# LED_Cube_MAX6966.net
KiCad netlist of a schematic drawn in EAGLE
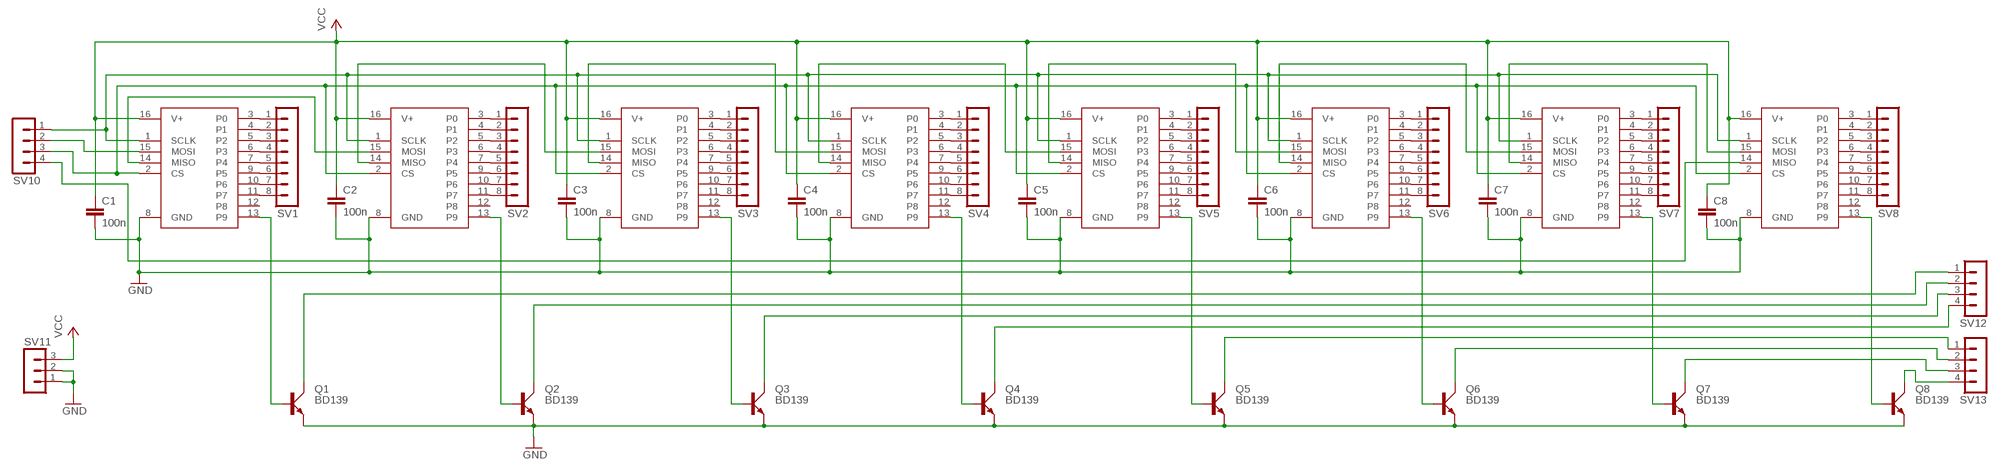
[diagram p0: schematic, sheet 1]

(export (version "E")
  (design (tool "Eeschema 10.0.6"))
  (components
    (comp (ref "C1")
      (value "100n")
      (footprint "eagle-import:C025_050-025X075")
      (libsource (lib "eagle-import") (part "C-EU025_050-025X075"))
    )
    (comp (ref "C2")
      (value "100n")
      (footprint "eagle-import:C025_050-025X075")
      (libsource (lib "eagle-import") (part "C-EU025_050-025X075"))
    )
    (comp (ref "C3")
      (value "100n")
      (footprint "eagle-import:C025_050-025X075")
      (libsource (lib "eagle-import") (part "C-EU025_050-025X075"))
    )
    (comp (ref "C4")
      (value "100n")
      (footprint "eagle-import:C025_050-025X075")
      (libsource (lib "eagle-import") (part "C-EU025_050-025X075"))
    )
    (comp (ref "C5")
      (value "100n")
      (footprint "eagle-import:C025_050-025X075")
      (libsource (lib "eagle-import") (part "C-EU025_050-025X075"))
    )
    (comp (ref "C6")
      (value "100n")
      (footprint "eagle-import:C025_050-025X075")
      (libsource (lib "eagle-import") (part "C-EU025_050-025X075"))
    )
    (comp (ref "C7")
      (value "100n")
      (footprint "eagle-import:C025_050-025X075")
      (libsource (lib "eagle-import") (part "C-EU025_050-025X075"))
    )
    (comp (ref "C8")
      (value "100n")
      (footprint "eagle-import:C025_050-025X075")
      (libsource (lib "eagle-import") (part "C-EU025_050-025X075"))
    )
    (comp (ref "Q1")
      (value "BD139")
      (footprint "eagle-import:TO126AV")
      (libsource (lib "eagle-import") (part "BD139"))
    )
    (comp (ref "Q2")
      (value "BD139")
      (footprint "eagle-import:TO126AV")
      (libsource (lib "eagle-import") (part "BD139"))
    )
    (comp (ref "Q3")
      (value "BD139")
      (footprint "eagle-import:TO126AV")
      (libsource (lib "eagle-import") (part "BD139"))
    )
    (comp (ref "Q4")
      (value "BD139")
      (footprint "eagle-import:TO126AV")
      (libsource (lib "eagle-import") (part "BD139"))
    )
    (comp (ref "Q5")
      (value "BD139")
      (footprint "eagle-import:TO126AV")
      (libsource (lib "eagle-import") (part "BD139"))
    )
    (comp (ref "Q6")
      (value "BD139")
      (footprint "eagle-import:TO126AV")
      (libsource (lib "eagle-import") (part "BD139"))
    )
    (comp (ref "Q7")
      (value "BD139")
      (footprint "eagle-import:TO126AV")
      (libsource (lib "eagle-import") (part "BD139"))
    )
    (comp (ref "Q8")
      (value "BD139")
      (footprint "eagle-import:TO126AV")
      (libsource (lib "eagle-import") (part "BD139"))
    )
    (comp (ref "SV1")
      (value "MA08-1")
      (footprint "eagle-import:MA08-1")
      (libsource (lib "eagle-import") (part "MA08-1"))
    )
    (comp (ref "SV2")
      (value "MA08-1")
      (footprint "eagle-import:MA08-1")
      (libsource (lib "eagle-import") (part "MA08-1"))
    )
    (comp (ref "SV3")
      (value "MA08-1")
      (footprint "eagle-import:MA08-1")
      (libsource (lib "eagle-import") (part "MA08-1"))
    )
    (comp (ref "SV4")
      (value "MA08-1")
      (footprint "eagle-import:MA08-1")
      (libsource (lib "eagle-import") (part "MA08-1"))
    )
    (comp (ref "SV5")
      (value "MA08-1")
      (footprint "eagle-import:MA08-1")
      (libsource (lib "eagle-import") (part "MA08-1"))
    )
    (comp (ref "SV6")
      (value "MA08-1")
      (footprint "eagle-import:MA08-1")
      (libsource (lib "eagle-import") (part "MA08-1"))
    )
    (comp (ref "SV7")
      (value "MA08-1")
      (footprint "eagle-import:MA08-1")
      (libsource (lib "eagle-import") (part "MA08-1"))
    )
    (comp (ref "SV8")
      (value "MA08-1")
      (footprint "eagle-import:MA08-1")
      (libsource (lib "eagle-import") (part "MA08-1"))
    )
    (comp (ref "SV10")
      (value "MA04-1")
      (footprint "eagle-import:MA04-1")
      (libsource (lib "eagle-import") (part "MA04-1"))
    )
    (comp (ref "SV11")
      (value "MA03-1")
      (footprint "eagle-import:MA03-1")
      (libsource (lib "eagle-import") (part "MA03-1"))
    )
    (comp (ref "SV12")
      (value "MA04-1")
      (footprint "eagle-import:MA04-1")
      (libsource (lib "eagle-import") (part "MA04-1"))
    )
    (comp (ref "SV13")
      (value "MA04-1")
      (footprint "eagle-import:MA04-1")
      (libsource (lib "eagle-import") (part "MA04-1"))
    )
    (comp (ref "U$1")
      (value "MAX6966")
      (footprint "eagle-import:QSOP16")
      (libsource (lib "eagle-import") (part "MAX6966"))
    )
    (comp (ref "U$2")
      (value "MAX6966")
      (footprint "eagle-import:QSOP16")
      (libsource (lib "eagle-import") (part "MAX6966"))
    )
    (comp (ref "U$3")
      (value "MAX6966")
      (footprint "eagle-import:QSOP16")
      (libsource (lib "eagle-import") (part "MAX6966"))
    )
    (comp (ref "U$4")
      (value "MAX6966")
      (footprint "eagle-import:QSOP16")
      (libsource (lib "eagle-import") (part "MAX6966"))
    )
    (comp (ref "U$5")
      (value "MAX6966")
      (footprint "eagle-import:QSOP16")
      (libsource (lib "eagle-import") (part "MAX6966"))
    )
    (comp (ref "U$6")
      (value "MAX6966")
      (footprint "eagle-import:QSOP16")
      (libsource (lib "eagle-import") (part "MAX6966"))
    )
    (comp (ref "U$7")
      (value "MAX6966")
      (footprint "eagle-import:QSOP16")
      (libsource (lib "eagle-import") (part "MAX6966"))
    )
    (comp (ref "U$8")
      (value "MAX6966")
      (footprint "eagle-import:QSOP16")
      (libsource (lib "eagle-import") (part "MAX6966"))
    )
  )
  (nets
    (net (code "1") (name "GND") (class "Default")
      (node (ref "C1") (pin "2") (pinfunction "2_2") (pintype "passive"))
      (node (ref "C2") (pin "2") (pinfunction "2_2") (pintype "passive"))
      (node (ref "C3") (pin "2") (pinfunction "2_2") (pintype "passive"))
      (node (ref "C4") (pin "2") (pinfunction "2_2") (pintype "passive"))
      (node (ref "C5") (pin "2") (pinfunction "2_2") (pintype "passive"))
      (node (ref "C6") (pin "2") (pinfunction "2_2") (pintype "passive"))
      (node (ref "C7") (pin "2") (pinfunction "2_2") (pintype "passive"))
      (node (ref "C8") (pin "2") (pinfunction "2_2") (pintype "passive"))
      (node (ref "Q1") (pin "E") (pinfunction "E_E") (pintype "passive"))
      (node (ref "Q2") (pin "E") (pinfunction "E_E") (pintype "passive"))
      (node (ref "Q3") (pin "E") (pinfunction "E_E") (pintype "passive"))
      (node (ref "Q4") (pin "E") (pinfunction "E_E") (pintype "passive"))
      (node (ref "Q5") (pin "E") (pinfunction "E_E") (pintype "passive"))
      (node (ref "Q6") (pin "E") (pinfunction "E_E") (pintype "passive"))
      (node (ref "Q7") (pin "E") (pinfunction "E_E") (pintype "passive"))
      (node (ref "Q8") (pin "E") (pinfunction "E_E") (pintype "passive"))
      (node (ref "SV11") (pin "1") (pinfunction "1_1") (pintype "passive"))
      (node (ref "SV11") (pin "2") (pinfunction "2_2") (pintype "passive"))
      (node (ref "U$1") (pin "8") (pinfunction "GND_8") (pintype "bidirectional"))
      (node (ref "U$2") (pin "8") (pinfunction "GND_8") (pintype "bidirectional"))
      (node (ref "U$3") (pin "8") (pinfunction "GND_8") (pintype "bidirectional"))
      (node (ref "U$4") (pin "8") (pinfunction "GND_8") (pintype "bidirectional"))
      (node (ref "U$5") (pin "8") (pinfunction "GND_8") (pintype "bidirectional"))
      (node (ref "U$6") (pin "8") (pinfunction "GND_8") (pintype "bidirectional"))
      (node (ref "U$7") (pin "8") (pinfunction "GND_8") (pintype "bidirectional"))
      (node (ref "U$8") (pin "8") (pinfunction "GND_8") (pintype "bidirectional"))
    )
    (net (code "2") (name "Net-(Q1-PadC)") (class "Default")
      (node (ref "Q1") (pin "C") (pinfunction "C_C") (pintype "passive"))
      (node (ref "SV12") (pin "1") (pinfunction "1_1") (pintype "passive"))
    )
    (net (code "3") (name "Net-(Q2-PadC)") (class "Default")
      (node (ref "Q2") (pin "C") (pinfunction "C_C") (pintype "passive"))
      (node (ref "SV12") (pin "2") (pinfunction "2_2") (pintype "passive"))
    )
    (net (code "4") (name "Net-(Q3-PadC)") (class "Default")
      (node (ref "Q3") (pin "C") (pinfunction "C_C") (pintype "passive"))
      (node (ref "SV12") (pin "3") (pinfunction "3_3") (pintype "passive"))
    )
    (net (code "5") (name "Net-(Q4-PadC)") (class "Default")
      (node (ref "Q4") (pin "C") (pinfunction "C_C") (pintype "passive"))
      (node (ref "SV12") (pin "4") (pinfunction "4_4") (pintype "passive"))
    )
    (net (code "6") (name "Net-(Q5-PadC)") (class "Default")
      (node (ref "Q5") (pin "C") (pinfunction "C_C") (pintype "passive"))
      (node (ref "SV13") (pin "1") (pinfunction "1_1") (pintype "passive"))
    )
    (net (code "7") (name "Net-(Q6-PadC)") (class "Default")
      (node (ref "Q6") (pin "C") (pinfunction "C_C") (pintype "passive"))
      (node (ref "SV13") (pin "2") (pinfunction "2_2") (pintype "passive"))
    )
    (net (code "8") (name "Net-(Q7-PadC)") (class "Default")
      (node (ref "Q7") (pin "C") (pinfunction "C_C") (pintype "passive"))
      (node (ref "SV13") (pin "3") (pinfunction "3_3") (pintype "passive"))
    )
    (net (code "9") (name "Net-(Q8-PadC)") (class "Default")
      (node (ref "Q8") (pin "C") (pinfunction "C_C") (pintype "passive"))
      (node (ref "SV13") (pin "4") (pinfunction "4_4") (pintype "passive"))
    )
    (net (code "10") (name "Net-(U$1-CS)") (class "Default")
      (node (ref "SV10") (pin "3") (pinfunction "3_3") (pintype "passive"))
      (node (ref "U$1") (pin "2") (pinfunction "CS_2") (pintype "bidirectional"))
      (node (ref "U$2") (pin "2") (pinfunction "CS_2") (pintype "bidirectional"))
      (node (ref "U$3") (pin "2") (pinfunction "CS_2") (pintype "bidirectional"))
      (node (ref "U$4") (pin "2") (pinfunction "CS_2") (pintype "bidirectional"))
      (node (ref "U$5") (pin "2") (pinfunction "CS_2") (pintype "bidirectional"))
      (node (ref "U$6") (pin "2") (pinfunction "CS_2") (pintype "bidirectional"))
      (node (ref "U$7") (pin "2") (pinfunction "CS_2") (pintype "bidirectional"))
      (node (ref "U$8") (pin "2") (pinfunction "CS_2") (pintype "bidirectional"))
    )
    (net (code "11") (name "Net-(U$1-MISO)") (class "Default")
      (node (ref "U$1") (pin "14") (pinfunction "MISO_14") (pintype "bidirectional"))
      (node (ref "U$2") (pin "15") (pinfunction "MOSI_15") (pintype "bidirectional"))
    )
    (net (code "12") (name "Net-(U$1-MOSI)") (class "Default")
      (node (ref "SV10") (pin "2") (pinfunction "2_2") (pintype "passive"))
      (node (ref "U$1") (pin "15") (pinfunction "MOSI_15") (pintype "bidirectional"))
    )
    (net (code "13") (name "Net-(U$1-P0)") (class "Default")
      (node (ref "SV1") (pin "1") (pinfunction "1_1") (pintype "passive"))
      (node (ref "U$1") (pin "3") (pinfunction "P0_3") (pintype "bidirectional"))
    )
    (net (code "14") (name "Net-(U$1-P1)") (class "Default")
      (node (ref "SV1") (pin "2") (pinfunction "2_2") (pintype "passive"))
      (node (ref "U$1") (pin "4") (pinfunction "P1_4") (pintype "bidirectional"))
    )
    (net (code "15") (name "Net-(U$1-P2)") (class "Default")
      (node (ref "SV1") (pin "3") (pinfunction "3_3") (pintype "passive"))
      (node (ref "U$1") (pin "5") (pinfunction "P2_5") (pintype "bidirectional"))
    )
    (net (code "16") (name "Net-(U$1-P3)") (class "Default")
      (node (ref "SV1") (pin "4") (pinfunction "4_4") (pintype "passive"))
      (node (ref "U$1") (pin "6") (pinfunction "P3_6") (pintype "bidirectional"))
    )
    (net (code "17") (name "Net-(U$1-P4)") (class "Default")
      (node (ref "SV1") (pin "5") (pinfunction "5_5") (pintype "passive"))
      (node (ref "U$1") (pin "7") (pinfunction "P4_7") (pintype "bidirectional"))
    )
    (net (code "18") (name "Net-(U$1-P5)") (class "Default")
      (node (ref "SV1") (pin "6") (pinfunction "6_6") (pintype "passive"))
      (node (ref "U$1") (pin "9") (pinfunction "P5_9") (pintype "bidirectional"))
    )
    (net (code "19") (name "Net-(U$1-P6)") (class "Default")
      (node (ref "SV1") (pin "7") (pinfunction "7_7") (pintype "passive"))
      (node (ref "U$1") (pin "10") (pinfunction "P6_10") (pintype "bidirectional"))
    )
    (net (code "20") (name "Net-(U$1-P7)") (class "Default")
      (node (ref "SV1") (pin "8") (pinfunction "8_8") (pintype "passive"))
      (node (ref "U$1") (pin "11") (pinfunction "P7_11") (pintype "bidirectional"))
    )
    (net (code "21") (name "Net-(U$1-P9)") (class "Default")
      (node (ref "Q1") (pin "B") (pinfunction "B_B") (pintype "passive"))
      (node (ref "U$1") (pin "13") (pinfunction "P9_13") (pintype "bidirectional"))
    )
    (net (code "22") (name "Net-(U$1-SCLK)") (class "Default")
      (node (ref "SV10") (pin "1") (pinfunction "1_1") (pintype "passive"))
      (node (ref "U$1") (pin "1") (pinfunction "SCLK_1") (pintype "bidirectional"))
      (node (ref "U$2") (pin "1") (pinfunction "SCLK_1") (pintype "bidirectional"))
      (node (ref "U$3") (pin "1") (pinfunction "SCLK_1") (pintype "bidirectional"))
      (node (ref "U$4") (pin "1") (pinfunction "SCLK_1") (pintype "bidirectional"))
      (node (ref "U$5") (pin "1") (pinfunction "SCLK_1") (pintype "bidirectional"))
      (node (ref "U$6") (pin "1") (pinfunction "SCLK_1") (pintype "bidirectional"))
      (node (ref "U$7") (pin "1") (pinfunction "SCLK_1") (pintype "bidirectional"))
      (node (ref "U$8") (pin "1") (pinfunction "SCLK_1") (pintype "bidirectional"))
    )
    (net (code "23") (name "Net-(U$2-MISO)") (class "Default")
      (node (ref "U$2") (pin "14") (pinfunction "MISO_14") (pintype "bidirectional"))
      (node (ref "U$3") (pin "15") (pinfunction "MOSI_15") (pintype "bidirectional"))
    )
    (net (code "24") (name "Net-(U$2-P0)") (class "Default")
      (node (ref "SV2") (pin "1") (pinfunction "1_1") (pintype "passive"))
      (node (ref "U$2") (pin "3") (pinfunction "P0_3") (pintype "bidirectional"))
    )
    (net (code "25") (name "Net-(U$2-P1)") (class "Default")
      (node (ref "SV2") (pin "2") (pinfunction "2_2") (pintype "passive"))
      (node (ref "U$2") (pin "4") (pinfunction "P1_4") (pintype "bidirectional"))
    )
    (net (code "26") (name "Net-(U$2-P2)") (class "Default")
      (node (ref "SV2") (pin "3") (pinfunction "3_3") (pintype "passive"))
      (node (ref "U$2") (pin "5") (pinfunction "P2_5") (pintype "bidirectional"))
    )
    (net (code "27") (name "Net-(U$2-P3)") (class "Default")
      (node (ref "SV2") (pin "4") (pinfunction "4_4") (pintype "passive"))
      (node (ref "U$2") (pin "6") (pinfunction "P3_6") (pintype "bidirectional"))
    )
    (net (code "28") (name "Net-(U$2-P4)") (class "Default")
      (node (ref "SV2") (pin "5") (pinfunction "5_5") (pintype "passive"))
      (node (ref "U$2") (pin "7") (pinfunction "P4_7") (pintype "bidirectional"))
    )
    (net (code "29") (name "Net-(U$2-P5)") (class "Default")
      (node (ref "SV2") (pin "6") (pinfunction "6_6") (pintype "passive"))
      (node (ref "U$2") (pin "9") (pinfunction "P5_9") (pintype "bidirectional"))
    )
    (net (code "30") (name "Net-(U$2-P6)") (class "Default")
      (node (ref "SV2") (pin "7") (pinfunction "7_7") (pintype "passive"))
      (node (ref "U$2") (pin "10") (pinfunction "P6_10") (pintype "bidirectional"))
    )
    (net (code "31") (name "Net-(U$2-P7)") (class "Default")
      (node (ref "SV2") (pin "8") (pinfunction "8_8") (pintype "passive"))
      (node (ref "U$2") (pin "11") (pinfunction "P7_11") (pintype "bidirectional"))
    )
    (net (code "32") (name "Net-(U$2-P9)") (class "Default")
      (node (ref "Q2") (pin "B") (pinfunction "B_B") (pintype "passive"))
      (node (ref "U$2") (pin "13") (pinfunction "P9_13") (pintype "bidirectional"))
    )
    (net (code "33") (name "Net-(U$3-MISO)") (class "Default")
      (node (ref "U$3") (pin "14") (pinfunction "MISO_14") (pintype "bidirectional"))
      (node (ref "U$4") (pin "15") (pinfunction "MOSI_15") (pintype "bidirectional"))
    )
    (net (code "34") (name "Net-(U$3-P0)") (class "Default")
      (node (ref "SV3") (pin "1") (pinfunction "1_1") (pintype "passive"))
      (node (ref "U$3") (pin "3") (pinfunction "P0_3") (pintype "bidirectional"))
    )
    (net (code "35") (name "Net-(U$3-P1)") (class "Default")
      (node (ref "SV3") (pin "2") (pinfunction "2_2") (pintype "passive"))
      (node (ref "U$3") (pin "4") (pinfunction "P1_4") (pintype "bidirectional"))
    )
    (net (code "36") (name "Net-(U$3-P2)") (class "Default")
      (node (ref "SV3") (pin "3") (pinfunction "3_3") (pintype "passive"))
      (node (ref "U$3") (pin "5") (pinfunction "P2_5") (pintype "bidirectional"))
    )
    (net (code "37") (name "Net-(U$3-P3)") (class "Default")
      (node (ref "SV3") (pin "4") (pinfunction "4_4") (pintype "passive"))
      (node (ref "U$3") (pin "6") (pinfunction "P3_6") (pintype "bidirectional"))
    )
    (net (code "38") (name "Net-(U$3-P4)") (class "Default")
      (node (ref "SV3") (pin "5") (pinfunction "5_5") (pintype "passive"))
      (node (ref "U$3") (pin "7") (pinfunction "P4_7") (pintype "bidirectional"))
    )
    (net (code "39") (name "Net-(U$3-P5)") (class "Default")
      (node (ref "SV3") (pin "6") (pinfunction "6_6") (pintype "passive"))
      (node (ref "U$3") (pin "9") (pinfunction "P5_9") (pintype "bidirectional"))
    )
    (net (code "40") (name "Net-(U$3-P6)") (class "Default")
      (node (ref "SV3") (pin "7") (pinfunction "7_7") (pintype "passive"))
      (node (ref "U$3") (pin "10") (pinfunction "P6_10") (pintype "bidirectional"))
    )
    (net (code "41") (name "Net-(U$3-P7)") (class "Default")
      (node (ref "SV3") (pin "8") (pinfunction "8_8") (pintype "passive"))
      (node (ref "U$3") (pin "11") (pinfunction "P7_11") (pintype "bidirectional"))
    )
    (net (code "42") (name "Net-(U$3-P9)") (class "Default")
      (node (ref "Q3") (pin "B") (pinfunction "B_B") (pintype "passive"))
      (node (ref "U$3") (pin "13") (pinfunction "P9_13") (pintype "bidirectional"))
    )
    (net (code "43") (name "Net-(U$4-MISO)") (class "Default")
      (node (ref "U$4") (pin "14") (pinfunction "MISO_14") (pintype "bidirectional"))
      (node (ref "U$5") (pin "15") (pinfunction "MOSI_15") (pintype "bidirectional"))
    )
    (net (code "44") (name "Net-(U$4-P0)") (class "Default")
      (node (ref "SV4") (pin "1") (pinfunction "1_1") (pintype "passive"))
      (node (ref "U$4") (pin "3") (pinfunction "P0_3") (pintype "bidirectional"))
    )
    (net (code "45") (name "Net-(U$4-P1)") (class "Default")
      (node (ref "SV4") (pin "2") (pinfunction "2_2") (pintype "passive"))
      (node (ref "U$4") (pin "4") (pinfunction "P1_4") (pintype "bidirectional"))
    )
    (net (code "46") (name "Net-(U$4-P2)") (class "Default")
      (node (ref "SV4") (pin "3") (pinfunction "3_3") (pintype "passive"))
      (node (ref "U$4") (pin "5") (pinfunction "P2_5") (pintype "bidirectional"))
    )
    (net (code "47") (name "Net-(U$4-P3)") (class "Default")
      (node (ref "SV4") (pin "4") (pinfunction "4_4") (pintype "passive"))
      (node (ref "U$4") (pin "6") (pinfunction "P3_6") (pintype "bidirectional"))
    )
    (net (code "48") (name "Net-(U$4-P4)") (class "Default")
      (node (ref "SV4") (pin "5") (pinfunction "5_5") (pintype "passive"))
      (node (ref "U$4") (pin "7") (pinfunction "P4_7") (pintype "bidirectional"))
    )
    (net (code "49") (name "Net-(U$4-P5)") (class "Default")
      (node (ref "SV4") (pin "6") (pinfunction "6_6") (pintype "passive"))
      (node (ref "U$4") (pin "9") (pinfunction "P5_9") (pintype "bidirectional"))
    )
    (net (code "50") (name "Net-(U$4-P6)") (class "Default")
      (node (ref "SV4") (pin "7") (pinfunction "7_7") (pintype "passive"))
      (node (ref "U$4") (pin "10") (pinfunction "P6_10") (pintype "bidirectional"))
    )
    (net (code "51") (name "Net-(U$4-P7)") (class "Default")
      (node (ref "SV4") (pin "8") (pinfunction "8_8") (pintype "passive"))
      (node (ref "U$4") (pin "11") (pinfunction "P7_11") (pintype "bidirectional"))
    )
    (net (code "52") (name "Net-(U$4-P9)") (class "Default")
      (node (ref "Q4") (pin "B") (pinfunction "B_B") (pintype "passive"))
      (node (ref "U$4") (pin "13") (pinfunction "P9_13") (pintype "bidirectional"))
    )
    (net (code "53") (name "Net-(U$5-MISO)") (class "Default")
      (node (ref "U$5") (pin "14") (pinfunction "MISO_14") (pintype "bidirectional"))
      (node (ref "U$6") (pin "15") (pinfunction "MOSI_15") (pintype "bidirectional"))
    )
    (net (code "54") (name "Net-(U$5-P0)") (class "Default")
      (node (ref "SV5") (pin "1") (pinfunction "1_1") (pintype "passive"))
      (node (ref "U$5") (pin "3") (pinfunction "P0_3") (pintype "bidirectional"))
    )
    (net (code "55") (name "Net-(U$5-P1)") (class "Default")
      (node (ref "SV5") (pin "2") (pinfunction "2_2") (pintype "passive"))
      (node (ref "U$5") (pin "4") (pinfunction "P1_4") (pintype "bidirectional"))
    )
    (net (code "56") (name "Net-(U$5-P2)") (class "Default")
      (node (ref "SV5") (pin "3") (pinfunction "3_3") (pintype "passive"))
      (node (ref "U$5") (pin "5") (pinfunction "P2_5") (pintype "bidirectional"))
    )
    (net (code "57") (name "Net-(U$5-P3)") (class "Default")
      (node (ref "SV5") (pin "4") (pinfunction "4_4") (pintype "passive"))
      (node (ref "U$5") (pin "6") (pinfunction "P3_6") (pintype "bidirectional"))
    )
    (net (code "58") (name "Net-(U$5-P4)") (class "Default")
      (node (ref "SV5") (pin "5") (pinfunction "5_5") (pintype "passive"))
      (node (ref "U$5") (pin "7") (pinfunction "P4_7") (pintype "bidirectional"))
    )
    (net (code "59") (name "Net-(U$5-P5)") (class "Default")
      (node (ref "SV5") (pin "6") (pinfunction "6_6") (pintype "passive"))
      (node (ref "U$5") (pin "9") (pinfunction "P5_9") (pintype "bidirectional"))
    )
    (net (code "60") (name "Net-(U$5-P6)") (class "Default")
      (node (ref "SV5") (pin "7") (pinfunction "7_7") (pintype "passive"))
      (node (ref "U$5") (pin "10") (pinfunction "P6_10") (pintype "bidirectional"))
    )
    (net (code "61") (name "Net-(U$5-P7)") (class "Default")
      (node (ref "SV5") (pin "8") (pinfunction "8_8") (pintype "passive"))
      (node (ref "U$5") (pin "11") (pinfunction "P7_11") (pintype "bidirectional"))
    )
    (net (code "62") (name "Net-(U$5-P9)") (class "Default")
      (node (ref "Q5") (pin "B") (pinfunction "B_B") (pintype "passive"))
      (node (ref "U$5") (pin "13") (pinfunction "P9_13") (pintype "bidirectional"))
    )
    (net (code "63") (name "Net-(U$6-MISO)") (class "Default")
      (node (ref "U$6") (pin "14") (pinfunction "MISO_14") (pintype "bidirectional"))
      (node (ref "U$7") (pin "15") (pinfunction "MOSI_15") (pintype "bidirectional"))
    )
    (net (code "64") (name "Net-(U$6-P0)") (class "Default")
      (node (ref "SV6") (pin "1") (pinfunction "1_1") (pintype "passive"))
      (node (ref "U$6") (pin "3") (pinfunction "P0_3") (pintype "bidirectional"))
    )
    (net (code "65") (name "Net-(U$6-P1)") (class "Default")
      (node (ref "SV6") (pin "2") (pinfunction "2_2") (pintype "passive"))
      (node (ref "U$6") (pin "4") (pinfunction "P1_4") (pintype "bidirectional"))
    )
    (net (code "66") (name "Net-(U$6-P2)") (class "Default")
      (node (ref "SV6") (pin "3") (pinfunction "3_3") (pintype "passive"))
      (node (ref "U$6") (pin "5") (pinfunction "P2_5") (pintype "bidirectional"))
    )
    (net (code "67") (name "Net-(U$6-P3)") (class "Default")
      (node (ref "SV6") (pin "4") (pinfunction "4_4") (pintype "passive"))
      (node (ref "U$6") (pin "6") (pinfunction "P3_6") (pintype "bidirectional"))
    )
    (net (code "68") (name "Net-(U$6-P4)") (class "Default")
      (node (ref "SV6") (pin "5") (pinfunction "5_5") (pintype "passive"))
      (node (ref "U$6") (pin "7") (pinfunction "P4_7") (pintype "bidirectional"))
    )
    (net (code "69") (name "Net-(U$6-P5)") (class "Default")
      (node (ref "SV6") (pin "6") (pinfunction "6_6") (pintype "passive"))
      (node (ref "U$6") (pin "9") (pinfunction "P5_9") (pintype "bidirectional"))
    )
    (net (code "70") (name "Net-(U$6-P6)") (class "Default")
      (node (ref "SV6") (pin "7") (pinfunction "7_7") (pintype "passive"))
      (node (ref "U$6") (pin "10") (pinfunction "P6_10") (pintype "bidirectional"))
    )
    (net (code "71") (name "Net-(U$6-P7)") (class "Default")
      (node (ref "SV6") (pin "8") (pinfunction "8_8") (pintype "passive"))
      (node (ref "U$6") (pin "11") (pinfunction "P7_11") (pintype "bidirectional"))
    )
    (net (code "72") (name "Net-(U$6-P9)") (class "Default")
      (node (ref "Q6") (pin "B") (pinfunction "B_B") (pintype "passive"))
      (node (ref "U$6") (pin "13") (pinfunction "P9_13") (pintype "bidirectional"))
    )
    (net (code "73") (name "Net-(U$7-MISO)") (class "Default")
      (node (ref "U$7") (pin "14") (pinfunction "MISO_14") (pintype "bidirectional"))
      (node (ref "U$8") (pin "15") (pinfunction "MOSI_15") (pintype "bidirectional"))
    )
    (net (code "74") (name "Net-(U$7-P0)") (class "Default")
      (node (ref "SV7") (pin "1") (pinfunction "1_1") (pintype "passive"))
      (node (ref "U$7") (pin "3") (pinfunction "P0_3") (pintype "bidirectional"))
    )
    (net (code "75") (name "Net-(U$7-P1)") (class "Default")
      (node (ref "SV7") (pin "2") (pinfunction "2_2") (pintype "passive"))
      (node (ref "U$7") (pin "4") (pinfunction "P1_4") (pintype "bidirectional"))
    )
    (net (code "76") (name "Net-(U$7-P2)") (class "Default")
      (node (ref "SV7") (pin "3") (pinfunction "3_3") (pintype "passive"))
      (node (ref "U$7") (pin "5") (pinfunction "P2_5") (pintype "bidirectional"))
    )
    (net (code "77") (name "Net-(U$7-P3)") (class "Default")
      (node (ref "SV7") (pin "4") (pinfunction "4_4") (pintype "passive"))
      (node (ref "U$7") (pin "6") (pinfunction "P3_6") (pintype "bidirectional"))
    )
    (net (code "78") (name "Net-(U$7-P4)") (class "Default")
      (node (ref "SV7") (pin "5") (pinfunction "5_5") (pintype "passive"))
      (node (ref "U$7") (pin "7") (pinfunction "P4_7") (pintype "bidirectional"))
    )
    (net (code "79") (name "Net-(U$7-P5)") (class "Default")
      (node (ref "SV7") (pin "6") (pinfunction "6_6") (pintype "passive"))
      (node (ref "U$7") (pin "9") (pinfunction "P5_9") (pintype "bidirectional"))
    )
    (net (code "80") (name "Net-(U$7-P6)") (class "Default")
      (node (ref "SV7") (pin "7") (pinfunction "7_7") (pintype "passive"))
      (node (ref "U$7") (pin "10") (pinfunction "P6_10") (pintype "bidirectional"))
    )
    (net (code "81") (name "Net-(U$7-P7)") (class "Default")
      (node (ref "SV7") (pin "8") (pinfunction "8_8") (pintype "passive"))
      (node (ref "U$7") (pin "11") (pinfunction "P7_11") (pintype "bidirectional"))
    )
    (net (code "82") (name "Net-(U$7-P9)") (class "Default")
      (node (ref "Q7") (pin "B") (pinfunction "B_B") (pintype "passive"))
      (node (ref "U$7") (pin "13") (pinfunction "P9_13") (pintype "bidirectional"))
    )
    (net (code "83") (name "Net-(U$8-MISO)") (class "Default")
      (node (ref "SV10") (pin "4") (pinfunction "4_4") (pintype "passive"))
      (node (ref "U$8") (pin "14") (pinfunction "MISO_14") (pintype "bidirectional"))
    )
    (net (code "84") (name "Net-(U$8-P0)") (class "Default")
      (node (ref "SV8") (pin "1") (pinfunction "1_1") (pintype "passive"))
      (node (ref "U$8") (pin "3") (pinfunction "P0_3") (pintype "bidirectional"))
    )
    (net (code "85") (name "Net-(U$8-P1)") (class "Default")
      (node (ref "SV8") (pin "2") (pinfunction "2_2") (pintype "passive"))
      (node (ref "U$8") (pin "4") (pinfunction "P1_4") (pintype "bidirectional"))
    )
    (net (code "86") (name "Net-(U$8-P2)") (class "Default")
      (node (ref "SV8") (pin "3") (pinfunction "3_3") (pintype "passive"))
      (node (ref "U$8") (pin "5") (pinfunction "P2_5") (pintype "bidirectional"))
    )
    (net (code "87") (name "Net-(U$8-P3)") (class "Default")
      (node (ref "SV8") (pin "4") (pinfunction "4_4") (pintype "passive"))
      (node (ref "U$8") (pin "6") (pinfunction "P3_6") (pintype "bidirectional"))
    )
    (net (code "88") (name "Net-(U$8-P4)") (class "Default")
      (node (ref "SV8") (pin "5") (pinfunction "5_5") (pintype "passive"))
      (node (ref "U$8") (pin "7") (pinfunction "P4_7") (pintype "bidirectional"))
    )
    (net (code "89") (name "Net-(U$8-P5)") (class "Default")
      (node (ref "SV8") (pin "6") (pinfunction "6_6") (pintype "passive"))
      (node (ref "U$8") (pin "9") (pinfunction "P5_9") (pintype "bidirectional"))
    )
    (net (code "90") (name "Net-(U$8-P6)") (class "Default")
      (node (ref "SV8") (pin "7") (pinfunction "7_7") (pintype "passive"))
      (node (ref "U$8") (pin "10") (pinfunction "P6_10") (pintype "bidirectional"))
    )
    (net (code "91") (name "Net-(U$8-P7)") (class "Default")
      (node (ref "SV8") (pin "8") (pinfunction "8_8") (pintype "passive"))
      (node (ref "U$8") (pin "11") (pinfunction "P7_11") (pintype "bidirectional"))
    )
    (net (code "92") (name "Net-(U$8-P9)") (class "Default")
      (node (ref "Q8") (pin "B") (pinfunction "B_B") (pintype "passive"))
      (node (ref "U$8") (pin "13") (pinfunction "P9_13") (pintype "bidirectional"))
    )
    (net (code "93") (name "VCC") (class "Default")
      (node (ref "C1") (pin "1") (pinfunction "1_1") (pintype "passive"))
      (node (ref "C2") (pin "1") (pinfunction "1_1") (pintype "passive"))
      (node (ref "C3") (pin "1") (pinfunction "1_1") (pintype "passive"))
      (node (ref "C4") (pin "1") (pinfunction "1_1") (pintype "passive"))
      (node (ref "C5") (pin "1") (pinfunction "1_1") (pintype "passive"))
      (node (ref "C6") (pin "1") (pinfunction "1_1") (pintype "passive"))
      (node (ref "C7") (pin "1") (pinfunction "1_1") (pintype "passive"))
      (node (ref "C8") (pin "1") (pinfunction "1_1") (pintype "passive"))
      (node (ref "SV11") (pin "3") (pinfunction "3_3") (pintype "passive"))
      (node (ref "U$1") (pin "16") (pinfunction "V+_16") (pintype "bidirectional"))
      (node (ref "U$2") (pin "16") (pinfunction "V+_16") (pintype "bidirectional"))
      (node (ref "U$3") (pin "16") (pinfunction "V+_16") (pintype "bidirectional"))
      (node (ref "U$4") (pin "16") (pinfunction "V+_16") (pintype "bidirectional"))
      (node (ref "U$5") (pin "16") (pinfunction "V+_16") (pintype "bidirectional"))
      (node (ref "U$6") (pin "16") (pinfunction "V+_16") (pintype "bidirectional"))
      (node (ref "U$7") (pin "16") (pinfunction "V+_16") (pintype "bidirectional"))
      (node (ref "U$8") (pin "16") (pinfunction "V+_16") (pintype "bidirectional"))
    )
    (net (code "94") (name "unconnected-(U$1-P8-Pad12)") (class "Default")
      (node (ref "U$1") (pin "12") (pinfunction "P8_12") (pintype "bidirectional"))
    )
    (net (code "95") (name "unconnected-(U$2-P8-Pad12)") (class "Default")
      (node (ref "U$2") (pin "12") (pinfunction "P8_12") (pintype "bidirectional"))
    )
    (net (code "96") (name "unconnected-(U$3-P8-Pad12)") (class "Default")
      (node (ref "U$3") (pin "12") (pinfunction "P8_12") (pintype "bidirectional"))
    )
    (net (code "97") (name "unconnected-(U$4-P8-Pad12)") (class "Default")
      (node (ref "U$4") (pin "12") (pinfunction "P8_12") (pintype "bidirectional"))
    )
    (net (code "98") (name "unconnected-(U$5-P8-Pad12)") (class "Default")
      (node (ref "U$5") (pin "12") (pinfunction "P8_12") (pintype "bidirectional"))
    )
    (net (code "99") (name "unconnected-(U$6-P8-Pad12)") (class "Default")
      (node (ref "U$6") (pin "12") (pinfunction "P8_12") (pintype "bidirectional"))
    )
    (net (code "100") (name "unconnected-(U$7-P8-Pad12)") (class "Default")
      (node (ref "U$7") (pin "12") (pinfunction "P8_12") (pintype "bidirectional"))
    )
    (net (code "101") (name "unconnected-(U$8-P8-Pad12)") (class "Default")
      (node (ref "U$8") (pin "12") (pinfunction "P8_12") (pintype "bidirectional"))
    )
  )
)
